# 13hdmi_lcd.net
KiCad netlist of a schematic drawn in Altium Designer
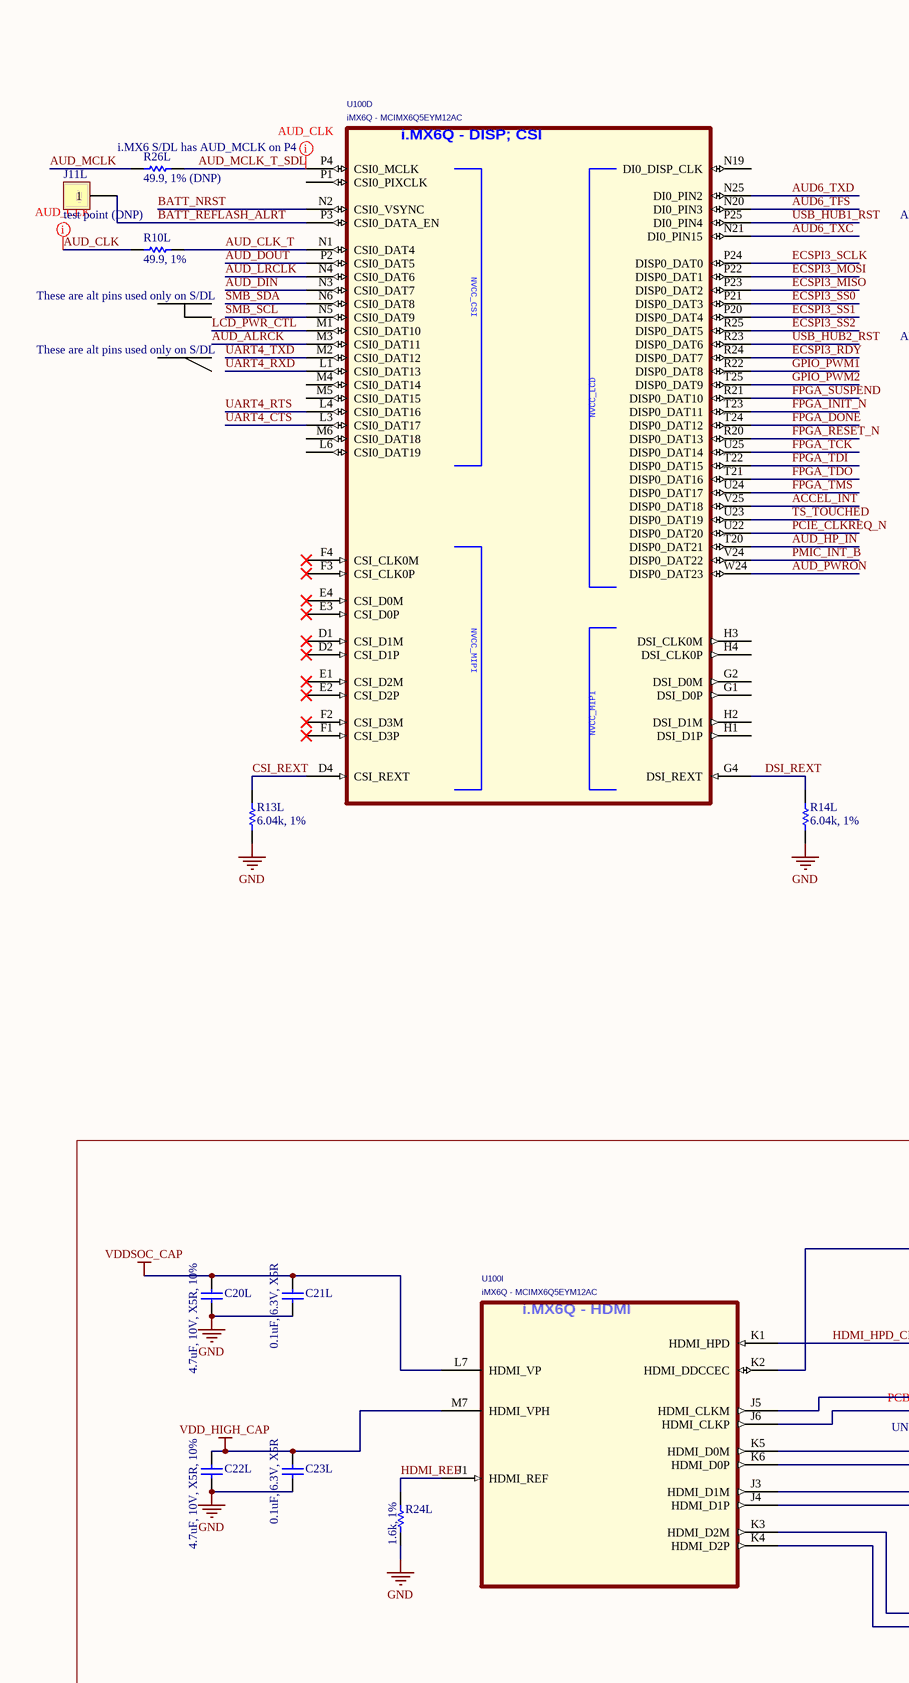
[diagram p0: 13hdmi_lcd.SchDoc, left]
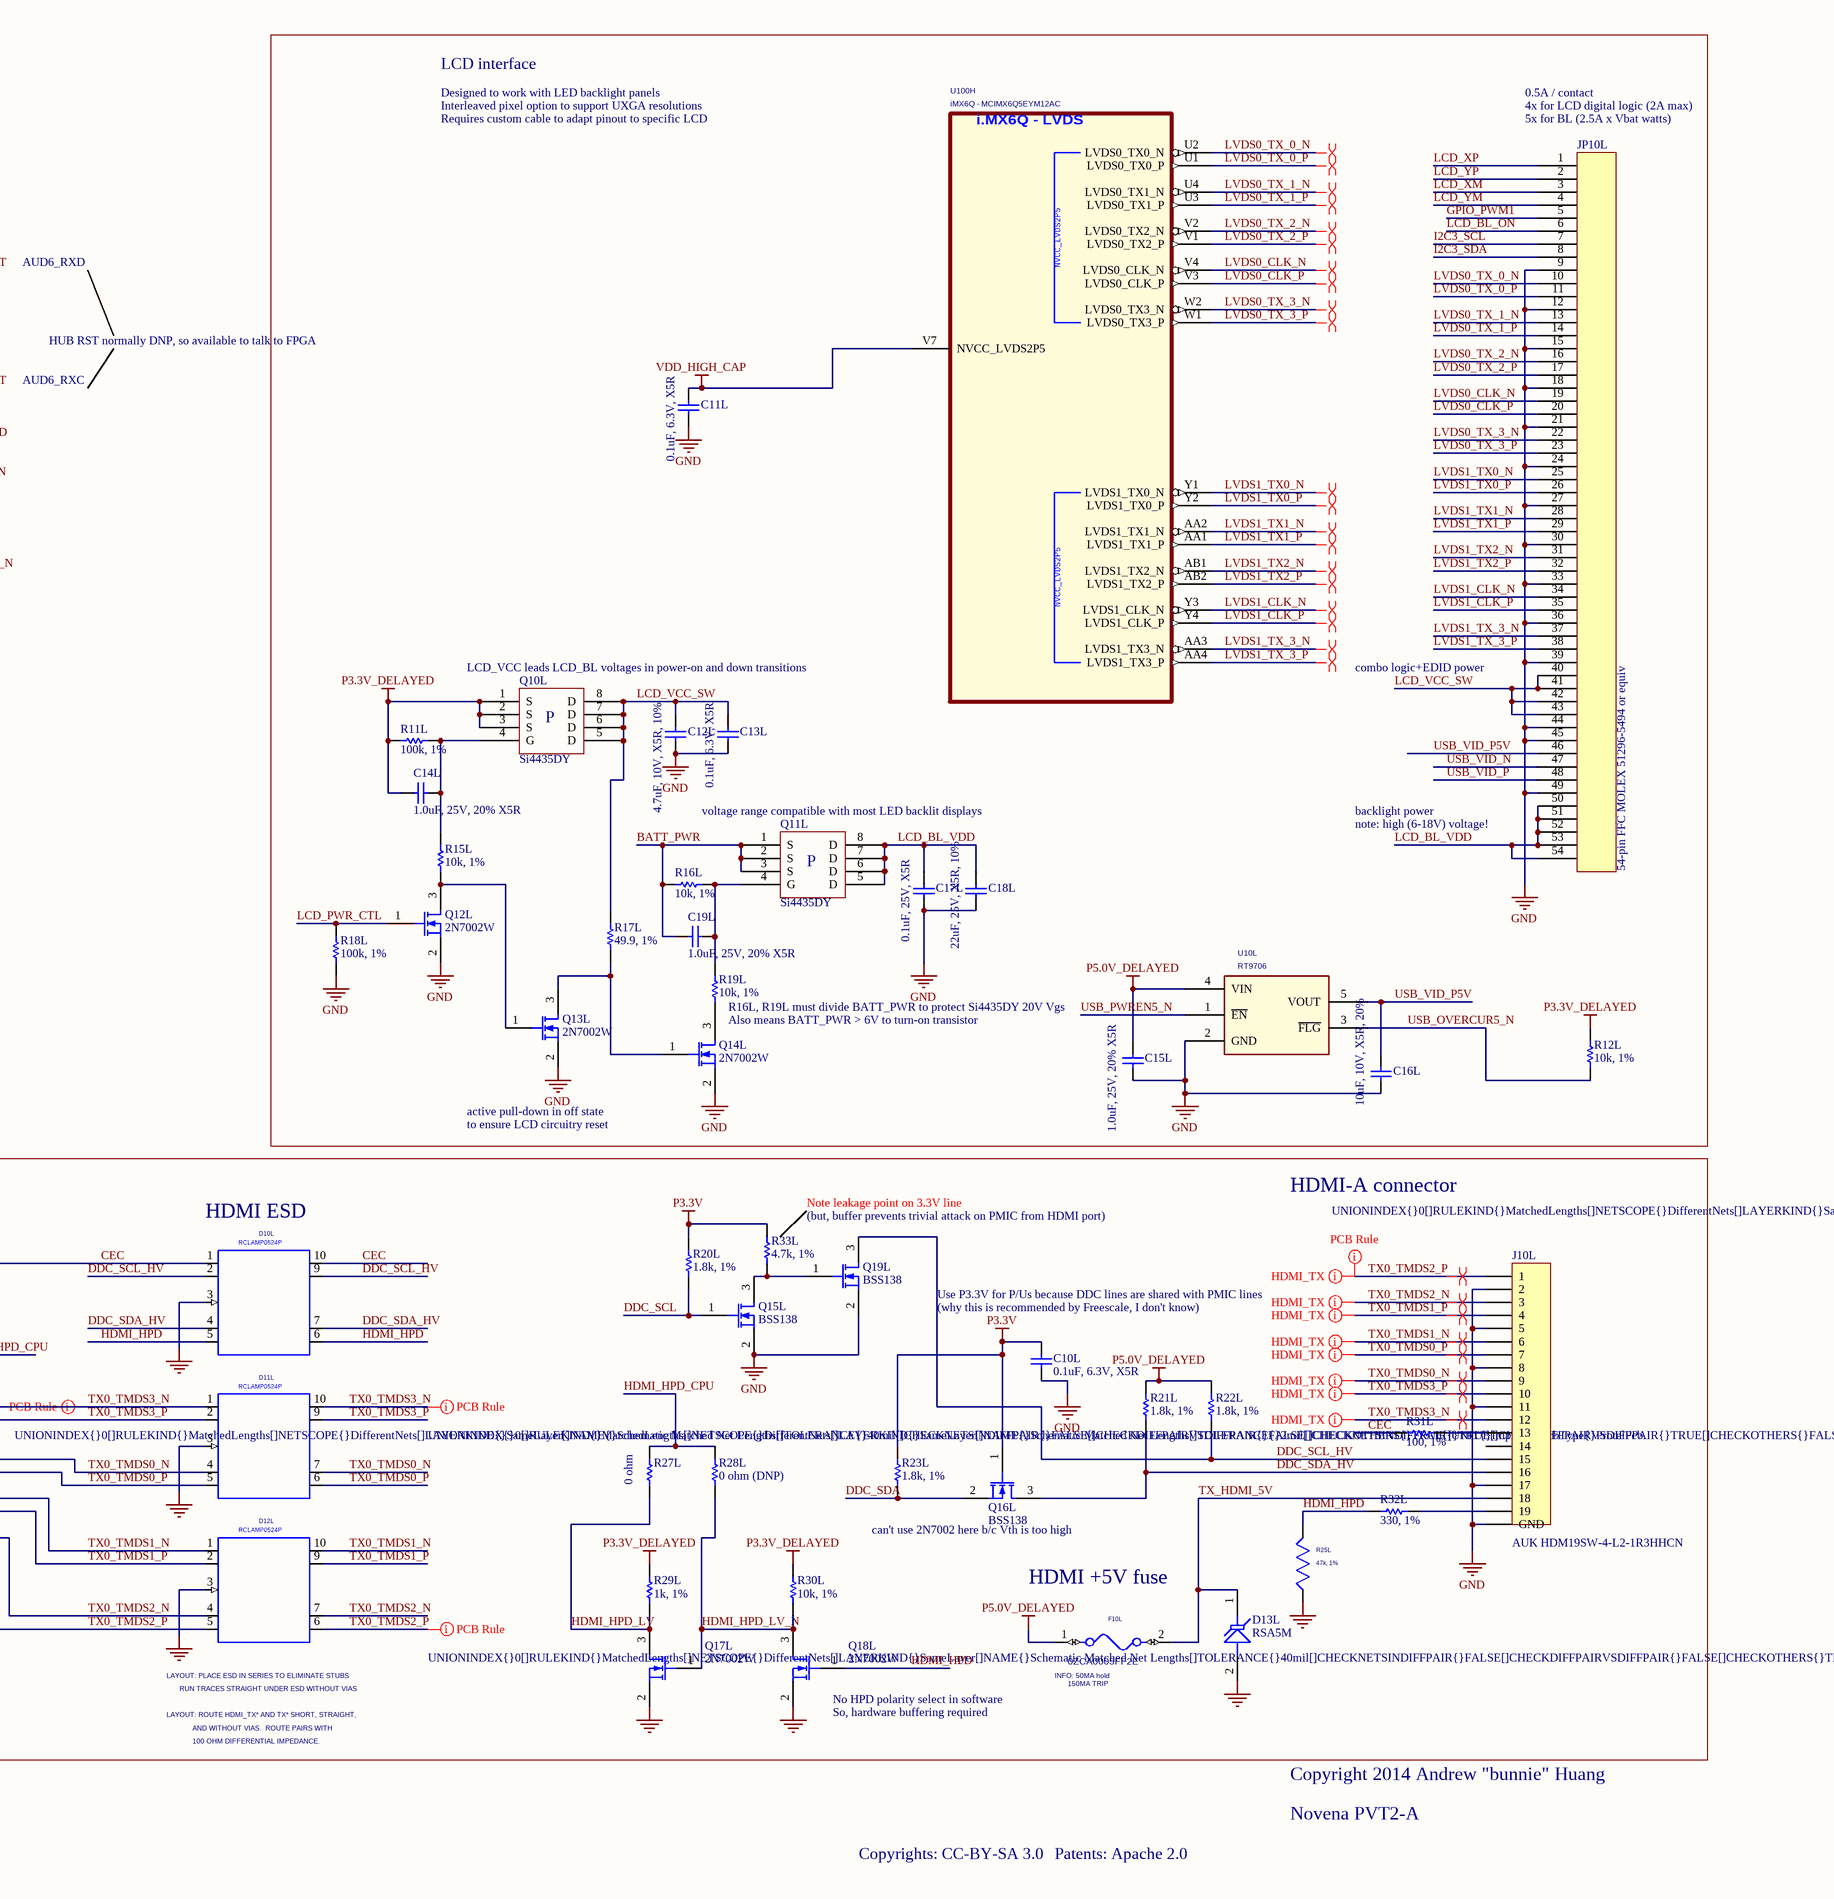
[diagram p1: 13hdmi_lcd.SchDoc, right]

(export (version "E")
  (design (tool "Eeschema 10.0.6"))
  (components
    (comp (ref "C10L")
      (value "0.1uF, 6.3V, X5R")
      (footprint "CAPC0603N_B")
      (description "Capacitor (Semiconductor SIM Model)")
      (fields (field (name "PUBLISHER") "Altium Limited"))
      (libsource (lib "Miscellaneous Devices") (part "Cap Semi"))
    )
    (comp (ref "C11L")
      (value "0.1uF, 6.3V, X5R")
      (footprint "CAPC0603N_B")
      (description "Capacitor (Semiconductor SIM Model)")
      (fields (field (name "PUBLISHER") "Altium Limited"))
      (libsource (lib "Miscellaneous Devices") (part "Cap Semi"))
    )
    (comp (ref "C12L")
      (value "4.7uF, 10V, X5R, 10%")
      (footprint "CAPC1608N")
      (description "Capacitor (Semiconductor SIM Model)")
      (fields (field (name "PUBLISHER") "Altium Limited"))
      (libsource (lib "Miscellaneous Devices") (part "Cap Semi"))
    )
    (comp (ref "C13L")
      (value "0.1uF, 6.3V, X5R")
      (footprint "CAPC0603N_B")
      (description "Capacitor (Semiconductor SIM Model)")
      (fields (field (name "PUBLISHER") "Altium Limited"))
      (libsource (lib "Miscellaneous Devices") (part "Cap Semi"))
    )
    (comp (ref "C14L")
      (value "1.0uF, 25V, 20% X5R")
      (footprint "CAPC1608N")
      (description "Capacitor (Semiconductor SIM Model)")
      (fields (field (name "PUBLISHER") "Altium Limited"))
      (libsource (lib "Miscellaneous Devices") (part "Cap Semi"))
    )
    (comp (ref "C15L")
      (value "1.0uF, 25V, 20% X5R")
      (footprint "CAPC1608N")
      (description "Capacitor (Semiconductor SIM Model)")
      (fields (field (name "PUBLISHER") "Altium Limited"))
      (libsource (lib "Miscellaneous Devices") (part "Cap Semi"))
    )
    (comp (ref "C16L")
      (value "10uF, 10V, X5R, 20%")
      (footprint "CAPC1608N")
      (description "Capacitor (Semiconductor SIM Model)")
      (fields (field (name "PUBLISHER") "Altium Limited"))
      (libsource (lib "Miscellaneous Devices") (part "Cap Semi"))
    )
    (comp (ref "C17L")
      (value "0.1uF, 25V, X5R")
      (footprint "CAPC1005N")
      (description "Capacitor (Semiconductor SIM Model)")
      (fields (field (name "PUBLISHER") "Altium Limited"))
      (libsource (lib "Miscellaneous Devices") (part "Cap Semi"))
    )
    (comp (ref "C18L")
      (value "22uF, 25V, X5R, 10%")
      (footprint "CAPC3225N")
      (description "Capacitor (Semiconductor SIM Model)")
      (fields (field (name "PUBLISHER") "Altium Limited"))
      (libsource (lib "Miscellaneous Devices") (part "Cap Semi"))
    )
    (comp (ref "C19L")
      (value "1.0uF, 25V, 20% X5R")
      (footprint "CAPC1608N")
      (description "Capacitor (Semiconductor SIM Model)")
      (fields (field (name "PUBLISHER") "Altium Limited"))
      (libsource (lib "Miscellaneous Devices") (part "Cap Semi"))
    )
    (comp (ref "C20L")
      (value "4.7uF, 10V, X5R, 10%")
      (footprint "CAPC1608N_HD")
      (description "Capacitor (Semiconductor SIM Model)")
      (fields (field (name "PUBLISHER") "Altium Limited"))
      (libsource (lib "Miscellaneous Devices") (part "Cap Semi"))
    )
    (comp (ref "C21L")
      (value "0.1uF, 6.3V, X5R")
      (footprint "CAPC0603N_B")
      (description "Capacitor (Semiconductor SIM Model)")
      (fields (field (name "PUBLISHER") "Altium Limited"))
      (libsource (lib "Miscellaneous Devices") (part "Cap Semi"))
    )
    (comp (ref "C22L")
      (value "4.7uF, 10V, X5R, 10%")
      (footprint "CAPC1608N_HD")
      (description "Capacitor (Semiconductor SIM Model)")
      (fields (field (name "PUBLISHER") "Altium Limited"))
      (libsource (lib "Miscellaneous Devices") (part "Cap Semi"))
    )
    (comp (ref "C23L")
      (value "0.1uF, 6.3V, X5R")
      (footprint "CAPC0603N_B")
      (description "Capacitor (Semiconductor SIM Model)")
      (fields (field (name "PUBLISHER") "Altium Limited"))
      (libsource (lib "Miscellaneous Devices") (part "Cap Semi"))
    )
    (comp (ref "D10L")
      (value "RCLAMP0524P")
      (fields (field (name "PART_NUMBER") "V00004-001"))
      (libsource (lib "*") (part "RCLAMP0524P"))
    )
    (comp (ref "D11L")
      (value "RCLAMP0524P")
      (fields (field (name "PART_NUMBER") "V00004-001"))
      (libsource (lib "*") (part "RCLAMP0524P"))
    )
    (comp (ref "D12L")
      (value "RCLAMP0524P")
      (fields (field (name "PART_NUMBER") "V00004-001"))
      (libsource (lib "*") (part "RCLAMP0524P"))
    )
    (comp (ref "D13L")
      (value "RSA5M")
      (footprint "SOD123/X.85")
      (description "Tranzorb")
      (fields (field (name "PUBLISHER") "Altium Limited"))
      (libsource (lib "Miscellaneous Devices") (part "Tranzorb"))
    )
    (comp (ref "F10L")
      (value "0ZCA0005FF2E")
      (description "BelFuse, 50mA hold, 150mA trip")
      (fields (field (name "PART_NUMBER") "M00014-001"))
      (libsource (lib "*") (part "FUSE0805"))
    )
    (comp (ref "J10L")
      (value "AUK HDM19SW-4-L2-1R3HHCN")
      (footprint "MOLEX_47151-0001")
      (description "Molex HDMI connector, Type A")
      (fields (field (name "PUBLISHER") "Altium Limited"))
      (libsource (lib "Miscellaneous Connectors") (part "Header 19"))
    )
    (comp (ref "J11L")
      (value "test point (DNP)")
      (footprint "TP_SMT_38mil")
      (description "Connector")
      (libsource (lib "*") (part "CON1"))
    )
    (comp (ref "JP10L")
      (value "54-pin FFC MOLEX 51296-5494 or equiv")
      (footprint "MOLEX_51296_5494")
      (description "Flat flex connector, 54 positions")
      (libsource (lib "commonsch") (part "HEADER_54"))
    )
    (comp (ref "Q10L")
      (value "Si4435DY")
      (footprint "SOIC127P600-8AN")
      (description "Singre P-channel FET, 8A, 30V")
      (libsource (lib "commonsch") (part "Si4435DY"))
    )
    (comp (ref "Q11L")
      (value "Si4435DY")
      (footprint "SOIC127P600-8AN")
      (description "Singre P-channel FET, 8A, 30V")
      (libsource (lib "commonsch") (part "Si4435DY"))
    )
    (comp (ref "Q12L")
      (value "2N7002W")
      (footprint "SOT323-3AN")
      (description "N-Channel MOSFET")
      (fields (field (name "PUBLISHER") "Altium Limited"))
      (libsource (lib "Miscellaneous Devices") (part "MOSFET-N"))
    )
    (comp (ref "Q13L")
      (value "2N7002W")
      (footprint "SOT323-3AN")
      (description "N-Channel MOSFET")
      (fields (field (name "PUBLISHER") "Altium Limited"))
      (libsource (lib "Miscellaneous Devices") (part "MOSFET-N"))
    )
    (comp (ref "Q14L")
      (value "2N7002W")
      (footprint "SOT323-3AN")
      (description "N-Channel MOSFET")
      (fields (field (name "PUBLISHER") "Altium Limited"))
      (libsource (lib "Miscellaneous Devices") (part "MOSFET-N"))
    )
    (comp (ref "Q15L")
      (value "BSS138")
      (footprint "SOT23-3N")
      (description "N-Channel MOSFET")
      (fields (field (name "PUBLISHER") "Altium Limited"))
      (libsource (lib "Miscellaneous Devices") (part "MOSFET-N"))
    )
    (comp (ref "Q16L")
      (value "BSS138")
      (footprint "SOT23-3N")
      (description "N-Channel MOSFET")
      (fields (field (name "PUBLISHER") "Altium Limited"))
      (libsource (lib "Miscellaneous Devices") (part "MOSFET-N"))
    )
    (comp (ref "Q17L")
      (value "2N7002W")
      (footprint "SOT323-3AN")
      (description "N-Channel MOSFET")
      (fields (field (name "PUBLISHER") "Altium Limited"))
      (libsource (lib "Miscellaneous Devices") (part "MOSFET-N"))
    )
    (comp (ref "Q18L")
      (value "2N7002W")
      (footprint "SOT323-3AN")
      (description "N-Channel MOSFET")
      (fields (field (name "PUBLISHER") "Altium Limited"))
      (libsource (lib "Miscellaneous Devices") (part "MOSFET-N"))
    )
    (comp (ref "Q19L")
      (value "BSS138")
      (footprint "SOT23-3N")
      (description "N-Channel MOSFET")
      (fields (field (name "PUBLISHER") "Altium Limited"))
      (libsource (lib "Miscellaneous Devices") (part "MOSFET-N"))
    )
    (comp (ref "R10L")
      (value "49.9, 1%")
      (footprint "RESC1005N")
      (description "Resistor")
      (fields (field (name "PUBLISHER") "Altium Limited"))
      (libsource (lib "Miscellaneous Devices") (part "Res1"))
    )
    (comp (ref "R11L")
      (value "100k, 1%")
      (footprint "RESC1005N")
      (description "Resistor")
      (fields (field (name "PUBLISHER") "Altium Limited"))
      (libsource (lib "Miscellaneous Devices") (part "Res1"))
    )
    (comp (ref "R12L")
      (value "10k, 1%")
      (footprint "RESC1005N")
      (description "Resistor")
      (fields (field (name "PUBLISHER") "Altium Limited"))
      (libsource (lib "Miscellaneous Devices") (part "Res1"))
    )
    (comp (ref "R13L")
      (value "6.04k, 1%")
      (footprint "RESC1005N")
      (description "Resistor")
      (fields (field (name "PUBLISHER") "Altium Limited"))
      (libsource (lib "Miscellaneous Devices") (part "Res1"))
    )
    (comp (ref "R14L")
      (value "6.04k, 1%")
      (footprint "RESC1005N")
      (description "Resistor")
      (fields (field (name "PUBLISHER") "Altium Limited"))
      (libsource (lib "Miscellaneous Devices") (part "Res1"))
    )
    (comp (ref "R15L")
      (value "10k, 1%")
      (footprint "RESC1005N")
      (description "Resistor")
      (fields (field (name "PUBLISHER") "Altium Limited"))
      (libsource (lib "Miscellaneous Devices") (part "Res1"))
    )
    (comp (ref "R16L")
      (value "10k, 1%")
      (footprint "RESC1005N")
      (description "Resistor")
      (fields (field (name "PUBLISHER") "Altium Limited"))
      (libsource (lib "Miscellaneous Devices") (part "Res1"))
    )
    (comp (ref "R17L")
      (value "49.9, 1%")
      (footprint "RESC1005N")
      (description "Resistor")
      (fields (field (name "PUBLISHER") "Altium Limited"))
      (libsource (lib "Miscellaneous Devices") (part "Res1"))
    )
    (comp (ref "R18L")
      (value "100k, 1%")
      (footprint "RESC1005N")
      (description "Resistor")
      (fields (field (name "PUBLISHER") "Altium Limited"))
      (libsource (lib "Miscellaneous Devices") (part "Res1"))
    )
    (comp (ref "R19L")
      (value "10k, 1%")
      (footprint "RESC1005N")
      (description "Resistor")
      (fields (field (name "PUBLISHER") "Altium Limited"))
      (libsource (lib "Miscellaneous Devices") (part "Res1"))
    )
    (comp (ref "R20L")
      (value "1.8k, 1%")
      (footprint "RESC1005N")
      (description "Resistor")
      (fields (field (name "PUBLISHER") "Altium Limited"))
      (libsource (lib "Miscellaneous Devices") (part "Res1"))
    )
    (comp (ref "R21L")
      (value "1.8k, 1%")
      (footprint "RESC1005N")
      (description "Resistor")
      (fields (field (name "PUBLISHER") "Altium Limited"))
      (libsource (lib "Miscellaneous Devices") (part "Res1"))
    )
    (comp (ref "R22L")
      (value "1.8k, 1%")
      (footprint "RESC1005N")
      (description "Resistor")
      (fields (field (name "PUBLISHER") "Altium Limited"))
      (libsource (lib "Miscellaneous Devices") (part "Res1"))
    )
    (comp (ref "R23L")
      (value "1.8k, 1%")
      (footprint "RESC1005N")
      (description "Resistor")
      (fields (field (name "PUBLISHER") "Altium Limited"))
      (libsource (lib "Miscellaneous Devices") (part "Res1"))
    )
    (comp (ref "R24L")
      (value "1.6k, 1%")
      (footprint "RESC1005N")
      (description "Resistor")
      (fields (field (name "PUBLISHER") "Altium Limited"))
      (libsource (lib "Miscellaneous Devices") (part "Res1"))
    )
    (comp (ref "R25L")
      (value "47k, 1%")
      (fields (field (name "PART_NUMBER") "D13015-001") (field (name "MFG") "PANASONIC"))
      (libsource (lib "*") (part "RES#1"))
    )
    (comp (ref "R26L")
      (value "49.9, 1% (DNP)")
      (footprint "RESC1005N")
      (description "Resistor")
      (fields (field (name "PUBLISHER") "Altium Limited"))
      (libsource (lib "Miscellaneous Devices") (part "Res1"))
    )
    (comp (ref "R27L")
      (value "0 ohm")
      (footprint "RESC1005N")
      (description "Resistor")
      (fields (field (name "PUBLISHER") "Altium Limited"))
      (libsource (lib "Miscellaneous Devices") (part "Res1"))
    )
    (comp (ref "R28L")
      (value "0 ohm (DNP)")
      (footprint "RESC1005N")
      (description "Resistor")
      (fields (field (name "PUBLISHER") "Altium Limited"))
      (libsource (lib "Miscellaneous Devices") (part "Res1"))
    )
    (comp (ref "R29L")
      (value "1k, 1%")
      (footprint "RESC1005N")
      (description "Resistor")
      (fields (field (name "PUBLISHER") "Altium Limited"))
      (libsource (lib "Miscellaneous Devices") (part "Res1"))
    )
    (comp (ref "R30L")
      (value "10k, 1%")
      (footprint "RESC1005N")
      (description "Resistor")
      (fields (field (name "PUBLISHER") "Altium Limited"))
      (libsource (lib "Miscellaneous Devices") (part "Res1"))
    )
    (comp (ref "R31L")
      (value "100, 1%")
      (footprint "RESC1005N")
      (description "Resistor")
      (fields (field (name "PUBLISHER") "Altium Limited"))
      (libsource (lib "Miscellaneous Devices") (part "Res1"))
    )
    (comp (ref "R32L")
      (value "330, 1%")
      (footprint "RESC1005N")
      (description "Resistor")
      (fields (field (name "PUBLISHER") "Altium Limited"))
      (libsource (lib "Miscellaneous Devices") (part "Res1"))
    )
    (comp (ref "R33L")
      (value "4.7k, 1%")
      (footprint "RESC1005N")
      (description "Resistor")
      (fields (field (name "PUBLISHER") "Altium Limited"))
      (libsource (lib "Miscellaneous Devices") (part "Res1"))
    )
    (comp (ref "U10L")
      (value "RT9706")
      (description "IC LIN SW W/FLAG 500MA 2.0-5.5V SOT23-5")
      (libsource (lib "*") (part "RT9706"))
    )
    (comp (ref "U100")
      (value "iMX6Q - MCIMX6Q5EYM12AC")
      (description "PCIMX6Q5EVT10AC")
      (libsource (lib "*") (part "PCIMX6Q6VV1A"))
    )
  )
  (nets
    (net (code "1") (name "/ACCEL_INT") (class "Default")
      (node (ref "U100") (pin "V25") (pinfunction "DISP0_DAT18_V25") (pintype "bidirectional"))
    )
    (net (code "2") (name "/AUD6_TFS") (class "Default")
      (node (ref "U100") (pin "N20") (pinfunction "DI0_PIN3_N20") (pintype "bidirectional"))
    )
    (net (code "3") (name "/AUD6_TXC") (class "Default")
      (node (ref "U100") (pin "N21") (pinfunction "DI0_PIN15_N21") (pintype "bidirectional"))
    )
    (net (code "4") (name "/AUD6_TXD") (class "Default")
      (node (ref "U100") (pin "N25") (pinfunction "DI0_PIN2_N25") (pintype "bidirectional"))
    )
    (net (code "5") (name "/AUD_ALRCK") (class "Default")
      (node (ref "U100") (pin "M3") (pinfunction "CSI0_DAT11_M3") (pintype "bidirectional"))
    )
    (net (code "6") (name "/AUD_CLK") (class "Default")
      (node (ref "R10L") (pin "2") (pinfunction "2_2") (pintype "passive"))
    )
    (net (code "7") (name "/AUD_CLK_T") (class "Default")
      (node (ref "R10L") (pin "1") (pinfunction "1_1") (pintype "passive"))
      (node (ref "U100") (pin "N1") (pinfunction "CSI0_DAT4_N1") (pintype "bidirectional"))
    )
    (net (code "8") (name "/AUD_DIN") (class "Default")
      (node (ref "U100") (pin "N3") (pinfunction "CSI0_DAT7_N3") (pintype "bidirectional"))
    )
    (net (code "9") (name "/AUD_DOUT") (class "Default")
      (node (ref "U100") (pin "P2") (pinfunction "CSI0_DAT5_P2") (pintype "bidirectional"))
    )
    (net (code "10") (name "/AUD_HP_IN") (class "Default")
      (node (ref "U100") (pin "T20") (pinfunction "DISP0_DAT21_T20") (pintype "bidirectional"))
    )
    (net (code "11") (name "/AUD_LRCLK") (class "Default")
      (node (ref "U100") (pin "N4") (pinfunction "CSI0_DAT6_N4") (pintype "bidirectional"))
    )
    (net (code "12") (name "/AUD_MCLK") (class "Default")
      (node (ref "R26L") (pin "2") (pinfunction "2_2") (pintype "passive"))
    )
    (net (code "13") (name "/AUD_MCLK_T_SDL") (class "Default")
      (node (ref "R26L") (pin "1") (pinfunction "1_1") (pintype "passive"))
      (node (ref "U100") (pin "P4") (pinfunction "CSI0_MCLK_P4") (pintype "bidirectional"))
    )
    (net (code "14") (name "/AUD_PWRON") (class "Default")
      (node (ref "U100") (pin "W24") (pinfunction "DISP0_DAT23_W24") (pintype "bidirectional"))
    )
    (net (code "15") (name "/BATT_NRST") (class "Default")
      (node (ref "U100") (pin "N2") (pinfunction "CSI0_VSYNC_N2") (pintype "bidirectional"))
    )
    (net (code "16") (name "/BATT_PWR") (class "Default")
      (node (ref "C19L") (pin "1") (pinfunction "1_1") (pintype "passive"))
      (node (ref "Q11L") (pin "1") (pinfunction "S_1") (pintype "passive"))
      (node (ref "Q11L") (pin "2") (pinfunction "S_2") (pintype "passive"))
      (node (ref "Q11L") (pin "3") (pinfunction "S_3") (pintype "passive"))
      (node (ref "R16L") (pin "2") (pinfunction "2_2") (pintype "passive"))
    )
    (net (code "17") (name "/BATT_REFLASH_ALRT") (class "Default")
      (node (ref "J11L") (pin "1") (pinfunction "1_1") (pintype "passive"))
      (node (ref "U100") (pin "P3") (pinfunction "CSI0_DATA_EN_P3") (pintype "bidirectional"))
    )
    (net (code "18") (name "/CEC") (class "Default")
      (node (ref "D10L") (pin "1") (pinfunction "IO1A_1") (pintype "bidirectional"))
      (node (ref "D10L") (pin "10") (pinfunction "IO1B_10") (pintype "bidirectional"))
      (node (ref "R31L") (pin "2") (pinfunction "2_2") (pintype "passive"))
      (node (ref "U100") (pin "K2") (pinfunction "HDMI_DDCCEC_K2") (pintype "bidirectional"))
    )
    (net (code "19") (name "/CSI_REXT") (class "Default")
      (node (ref "R13L") (pin "1") (pinfunction "1_1") (pintype "passive"))
      (node (ref "U100") (pin "D4") (pinfunction "CSI_REXT_D4") (pintype "input"))
    )
    (net (code "20") (name "/DDC_SCL") (class "Default")
      (node (ref "Q15L") (pin "1") (pinfunction "G_1") (pintype "passive"))
      (node (ref "R20L") (pin "2") (pinfunction "2_2") (pintype "passive"))
    )
    (net (code "21") (name "/DDC_SCL_HV") (class "Default")
      (node (ref "D10L") (pin "2") (pinfunction "IO2A_2") (pintype "bidirectional"))
      (node (ref "D10L") (pin "9") (pinfunction "IO2B_9") (pintype "bidirectional"))
      (node (ref "J10L") (pin "15") (pinfunction "15_15") (pintype "passive"))
      (node (ref "Q19L") (pin "3") (pinfunction "D_3") (pintype "passive"))
      (node (ref "R22L") (pin "2") (pinfunction "2_2") (pintype "passive"))
    )
    (net (code "22") (name "/DDC_SDA") (class "Default")
      (node (ref "Q16L") (pin "2") (pinfunction "S_2") (pintype "passive"))
      (node (ref "R23L") (pin "2") (pinfunction "2_2") (pintype "passive"))
    )
    (net (code "23") (name "/DDC_SDA_HV") (class "Default")
      (node (ref "D10L") (pin "4") (pinfunction "IO3A_4") (pintype "bidirectional"))
      (node (ref "D10L") (pin "7") (pinfunction "IO3B_7") (pintype "bidirectional"))
      (node (ref "J10L") (pin "16") (pinfunction "16_16") (pintype "passive"))
      (node (ref "Q16L") (pin "3") (pinfunction "D_3") (pintype "passive"))
      (node (ref "R21L") (pin "2") (pinfunction "2_2") (pintype "passive"))
    )
    (net (code "24") (name "/DSI_REXT") (class "Default")
      (node (ref "R14L") (pin "1") (pinfunction "1_1") (pintype "passive"))
      (node (ref "U100") (pin "G4") (pinfunction "DSI_REXT_G4") (pintype "input"))
    )
    (net (code "25") (name "/ECSPI3_MISO") (class "Default")
      (node (ref "U100") (pin "P23") (pinfunction "DISP0_DAT2_P23") (pintype "bidirectional"))
    )
    (net (code "26") (name "/ECSPI3_MOSI") (class "Default")
      (node (ref "U100") (pin "P22") (pinfunction "DISP0_DAT1_P22") (pintype "bidirectional"))
    )
    (net (code "27") (name "/ECSPI3_RDY") (class "Default")
      (node (ref "U100") (pin "R24") (pinfunction "DISP0_DAT7_R24") (pintype "bidirectional"))
    )
    (net (code "28") (name "/ECSPI3_SCLK") (class "Default")
      (node (ref "U100") (pin "P24") (pinfunction "DISP0_DAT0_P24") (pintype "bidirectional"))
    )
    (net (code "29") (name "/ECSPI3_SS0") (class "Default")
      (node (ref "U100") (pin "P21") (pinfunction "DISP0_DAT3_P21") (pintype "bidirectional"))
    )
    (net (code "30") (name "/ECSPI3_SS1") (class "Default")
      (node (ref "U100") (pin "P20") (pinfunction "DISP0_DAT4_P20") (pintype "bidirectional"))
    )
    (net (code "31") (name "/ECSPI3_SS2") (class "Default")
      (node (ref "U100") (pin "R25") (pinfunction "DISP0_DAT5_R25") (pintype "bidirectional"))
    )
    (net (code "32") (name "/FPGA_DONE") (class "Default")
      (node (ref "U100") (pin "T24") (pinfunction "DISP0_DAT12_T24") (pintype "bidirectional"))
    )
    (net (code "33") (name "/FPGA_INIT_N") (class "Default")
      (node (ref "U100") (pin "T23") (pinfunction "DISP0_DAT11_T23") (pintype "bidirectional"))
    )
    (net (code "34") (name "/FPGA_RESET_N") (class "Default")
      (node (ref "U100") (pin "R20") (pinfunction "DISP0_DAT13_R20") (pintype "bidirectional"))
    )
    (net (code "35") (name "/FPGA_SUSPEND") (class "Default")
      (node (ref "U100") (pin "R21") (pinfunction "DISP0_DAT10_R21") (pintype "bidirectional"))
    )
    (net (code "36") (name "/FPGA_TCK") (class "Default")
      (node (ref "U100") (pin "U25") (pinfunction "DISP0_DAT14_U25") (pintype "bidirectional"))
    )
    (net (code "37") (name "/FPGA_TDI") (class "Default")
      (node (ref "U100") (pin "T22") (pinfunction "DISP0_DAT15_T22") (pintype "bidirectional"))
    )
    (net (code "38") (name "/FPGA_TDO") (class "Default")
      (node (ref "U100") (pin "T21") (pinfunction "DISP0_DAT16_T21") (pintype "bidirectional"))
    )
    (net (code "39") (name "/FPGA_TMS") (class "Default")
      (node (ref "U100") (pin "U24") (pinfunction "DISP0_DAT17_U24") (pintype "bidirectional"))
    )
    (net (code "40") (name "/GPIO_PWM1") (class "Default")
      (node (ref "JP10L") (pin "5") (pintype "passive"))
      (node (ref "U100") (pin "R22") (pinfunction "DISP0_DAT8_R22") (pintype "bidirectional"))
    )
    (net (code "41") (name "/GPIO_PWM2") (class "Default")
      (node (ref "U100") (pin "T25") (pinfunction "DISP0_DAT9_T25") (pintype "bidirectional"))
    )
    (net (code "42") (name "/HDMI_HPD") (class "Default")
      (node (ref "D10L") (pin "5") (pinfunction "IO4A_5") (pintype "bidirectional"))
      (node (ref "D10L") (pin "6") (pinfunction "IO4B_6") (pintype "bidirectional"))
      (node (ref "Q18L") (pin "1") (pinfunction "G_1") (pintype "passive"))
      (node (ref "R25L") (pin "1") (pinfunction "A_1") (pintype "bidirectional"))
      (node (ref "R32L") (pin "2") (pinfunction "2_2") (pintype "passive"))
    )
    (net (code "43") (name "/HDMI_HPD_CPU") (class "Default")
      (node (ref "R27L") (pin "1") (pinfunction "1_1") (pintype "passive"))
      (node (ref "R28L") (pin "1") (pinfunction "1_1") (pintype "passive"))
      (node (ref "U100") (pin "K1") (pinfunction "HDMI_HPD_K1") (pintype "input"))
    )
    (net (code "44") (name "/HDMI_HPD_LV") (class "Default")
      (node (ref "Q17L") (pin "3") (pinfunction "D_3") (pintype "passive"))
      (node (ref "R27L") (pin "2") (pinfunction "2_2") (pintype "passive"))
      (node (ref "R29L") (pin "2") (pinfunction "2_2") (pintype "passive"))
    )
    (net (code "45") (name "/HDMI_HPD_LV_N") (class "Default")
      (node (ref "Q17L") (pin "1") (pinfunction "G_1") (pintype "passive"))
      (node (ref "Q18L") (pin "3") (pinfunction "D_3") (pintype "passive"))
      (node (ref "R28L") (pin "2") (pinfunction "2_2") (pintype "passive"))
      (node (ref "R30L") (pin "2") (pinfunction "2_2") (pintype "passive"))
    )
    (net (code "46") (name "/HDMI_REF") (class "Default")
      (node (ref "R24L") (pin "2") (pinfunction "2_2") (pintype "passive"))
      (node (ref "U100") (pin "J1") (pinfunction "HDMI_REF_J1") (pintype "input"))
    )
    (net (code "47") (name "/I2C3_SCL") (class "Default") (node (ref "JP10L") (pin "7") (pintype "passive")))
    (net (code "48") (name "/I2C3_SDA") (class "Default") (node (ref "JP10L") (pin "8") (pintype "passive")))
    (net (code "49") (name "/LCD_BL_ON") (class "Default") (node (ref "JP10L") (pin "6") (pintype "passive")))
    (net (code "50") (name "/LCD_BL_VDD") (class "Default")
      (node (ref "C17L") (pin "1") (pinfunction "1_1") (pintype "passive"))
      (node (ref "C18L") (pin "1") (pinfunction "1_1") (pintype "passive"))
      (node (ref "JP10L") (pin "50") (pintype "passive"))
      (node (ref "JP10L") (pin "51") (pintype "passive"))
      (node (ref "JP10L") (pin "52") (pintype "passive"))
      (node (ref "JP10L") (pin "53") (pintype "passive"))
      (node (ref "JP10L") (pin "54") (pintype "passive"))
      (node (ref "Q11L") (pin "5") (pinfunction "D_5") (pintype "passive"))
      (node (ref "Q11L") (pin "6") (pinfunction "D_6") (pintype "passive"))
      (node (ref "Q11L") (pin "7") (pinfunction "D_7") (pintype "passive"))
      (node (ref "Q11L") (pin "8") (pinfunction "D_8") (pintype "passive"))
    )
    (net (code "51") (name "/LCD_PWR_CTL") (class "Default")
      (node (ref "Q12L") (pin "1") (pinfunction "G_1") (pintype "passive"))
      (node (ref "R18L") (pin "2") (pinfunction "2_2") (pintype "passive"))
      (node (ref "U100") (pin "M1") (pinfunction "CSI0_DAT10_M1") (pintype "bidirectional"))
    )
    (net (code "52") (name "/LCD_VCC_SW") (class "Default")
      (node (ref "C12L") (pin "1") (pinfunction "1_1") (pintype "passive"))
      (node (ref "C13L") (pin "1") (pinfunction "1_1") (pintype "passive"))
      (node (ref "JP10L") (pin "40") (pintype "passive"))
      (node (ref "JP10L") (pin "41") (pintype "passive"))
      (node (ref "JP10L") (pin "42") (pintype "passive"))
      (node (ref "JP10L") (pin "43") (pintype "passive"))
      (node (ref "Q10L") (pin "5") (pinfunction "D_5") (pintype "passive"))
      (node (ref "Q10L") (pin "6") (pinfunction "D_6") (pintype "passive"))
      (node (ref "Q10L") (pin "7") (pinfunction "D_7") (pintype "passive"))
      (node (ref "Q10L") (pin "8") (pinfunction "D_8") (pintype "passive"))
      (node (ref "R17L") (pin "2") (pinfunction "2_2") (pintype "passive"))
    )
    (net (code "53") (name "/LCD_XM") (class "Default") (node (ref "JP10L") (pin "3") (pintype "passive")))
    (net (code "54") (name "/LCD_XP") (class "Default") (node (ref "JP10L") (pin "1") (pintype "passive")))
    (net (code "55") (name "/LCD_YM") (class "Default") (node (ref "JP10L") (pin "4") (pintype "passive")))
    (net (code "56") (name "/LCD_YP") (class "Default") (node (ref "JP10L") (pin "2") (pintype "passive")))
    (net (code "57") (name "/LVDS0_CLK_N") (class "Default")
      (node (ref "JP10L") (pin "19") (pintype "passive"))
      (node (ref "U100") (pin "V4") (pinfunction "LVDS0_CLK_N_V4") (pintype "output"))
    )
    (net (code "58") (name "/LVDS0_CLK_P") (class "Default")
      (node (ref "JP10L") (pin "20") (pintype "passive"))
      (node (ref "U100") (pin "V3") (pinfunction "LVDS0_CLK_P_V3") (pintype "output"))
    )
    (net (code "59") (name "/LVDS0_TX_0_N") (class "Default")
      (node (ref "JP10L") (pin "10") (pintype "passive"))
      (node (ref "U100") (pin "U2") (pinfunction "LVDS0_TX0_N_U2") (pintype "output"))
    )
    (net (code "60") (name "/LVDS0_TX_0_P") (class "Default")
      (node (ref "JP10L") (pin "11") (pintype "passive"))
      (node (ref "U100") (pin "U1") (pinfunction "LVDS0_TX0_P_U1") (pintype "output"))
    )
    (net (code "61") (name "/LVDS0_TX_1_N") (class "Default")
      (node (ref "JP10L") (pin "13") (pintype "passive"))
      (node (ref "U100") (pin "U4") (pinfunction "LVDS0_TX1_N_U4") (pintype "output"))
    )
    (net (code "62") (name "/LVDS0_TX_1_P") (class "Default")
      (node (ref "JP10L") (pin "14") (pintype "passive"))
      (node (ref "U100") (pin "U3") (pinfunction "LVDS0_TX1_P_U3") (pintype "output"))
    )
    (net (code "63") (name "/LVDS0_TX_2_N") (class "Default")
      (node (ref "JP10L") (pin "16") (pintype "passive"))
      (node (ref "U100") (pin "V2") (pinfunction "LVDS0_TX2_N_V2") (pintype "output"))
    )
    (net (code "64") (name "/LVDS0_TX_2_P") (class "Default")
      (node (ref "JP10L") (pin "17") (pintype "passive"))
      (node (ref "U100") (pin "V1") (pinfunction "LVDS0_TX2_P_V1") (pintype "output"))
    )
    (net (code "65") (name "/LVDS0_TX_3_N") (class "Default")
      (node (ref "JP10L") (pin "22") (pintype "passive"))
      (node (ref "U100") (pin "W2") (pinfunction "LVDS0_TX3_N_W2") (pintype "output"))
    )
    (net (code "66") (name "/LVDS0_TX_3_P") (class "Default")
      (node (ref "JP10L") (pin "23") (pintype "passive"))
      (node (ref "U100") (pin "W1") (pinfunction "LVDS0_TX3_P_W1") (pintype "output"))
    )
    (net (code "67") (name "/LVDS1_CLK_N") (class "Default")
      (node (ref "JP10L") (pin "34") (pintype "passive"))
      (node (ref "U100") (pin "Y3") (pinfunction "LVDS1_CLK_N_Y3") (pintype "output"))
    )
    (net (code "68") (name "/LVDS1_CLK_P") (class "Default")
      (node (ref "JP10L") (pin "35") (pintype "passive"))
      (node (ref "U100") (pin "Y4") (pinfunction "LVDS1_CLK_P_Y4") (pintype "output"))
    )
    (net (code "69") (name "/LVDS1_TX0_N") (class "Default")
      (node (ref "JP10L") (pin "25") (pintype "passive"))
      (node (ref "U100") (pin "Y1") (pinfunction "LVDS1_TX0_N_Y1") (pintype "output"))
    )
    (net (code "70") (name "/LVDS1_TX0_P") (class "Default")
      (node (ref "JP10L") (pin "26") (pintype "passive"))
      (node (ref "U100") (pin "Y2") (pinfunction "LVDS1_TX0_P_Y2") (pintype "output"))
    )
    (net (code "71") (name "/LVDS1_TX1_N") (class "Default")
      (node (ref "JP10L") (pin "28") (pintype "passive"))
      (node (ref "U100") (pin "AA2") (pinfunction "LVDS1_TX1_N_AA2") (pintype "output"))
    )
    (net (code "72") (name "/LVDS1_TX1_P") (class "Default")
      (node (ref "JP10L") (pin "29") (pintype "passive"))
      (node (ref "U100") (pin "AA1") (pinfunction "LVDS1_TX1_P_AA1") (pintype "output"))
    )
    (net (code "73") (name "/LVDS1_TX2_N") (class "Default")
      (node (ref "JP10L") (pin "31") (pintype "passive"))
      (node (ref "U100") (pin "AB1") (pinfunction "LVDS1_TX2_N_AB1") (pintype "output"))
    )
    (net (code "74") (name "/LVDS1_TX2_P") (class "Default")
      (node (ref "JP10L") (pin "32") (pintype "passive"))
      (node (ref "U100") (pin "AB2") (pinfunction "LVDS1_TX2_P_AB2") (pintype "output"))
    )
    (net (code "75") (name "/LVDS1_TX_3_N") (class "Default")
      (node (ref "JP10L") (pin "37") (pintype "passive"))
      (node (ref "U100") (pin "AA3") (pinfunction "LVDS1_TX3_N_AA3") (pintype "output"))
    )
    (net (code "76") (name "/LVDS1_TX_3_P") (class "Default")
      (node (ref "JP10L") (pin "38") (pintype "passive"))
      (node (ref "U100") (pin "AA4") (pinfunction "LVDS1_TX3_P_AA4") (pintype "output"))
    )
    (net (code "77") (name "/PCIE_CLKREQ_N") (class "Default")
      (node (ref "U100") (pin "U22") (pinfunction "DISP0_DAT20_U22") (pintype "bidirectional"))
    )
    (net (code "78") (name "/PMIC_INT_B") (class "Default")
      (node (ref "U100") (pin "V24") (pinfunction "DISP0_DAT22_V24") (pintype "bidirectional"))
    )
    (net (code "79") (name "/SMB_SCL") (class "Default")
      (node (ref "U100") (pin "N5") (pinfunction "CSI0_DAT9_N5") (pintype "bidirectional"))
    )
    (net (code "80") (name "/SMB_SDA") (class "Default")
      (node (ref "U100") (pin "N6") (pinfunction "CSI0_DAT8_N6") (pintype "bidirectional"))
    )
    (net (code "81") (name "/TS_TOUCHED") (class "Default")
      (node (ref "U100") (pin "U23") (pinfunction "DISP0_DAT19_U23") (pintype "bidirectional"))
    )
    (net (code "82") (name "/TX0_TMDS0_N") (class "Default")
      (node (ref "D11L") (pin "4") (pinfunction "IO3A_4") (pintype "bidirectional"))
      (node (ref "D11L") (pin "7") (pinfunction "IO3B_7") (pintype "bidirectional"))
      (node (ref "J10L") (pin "9") (pinfunction "9_9") (pintype "passive"))
      (node (ref "U100") (pin "K5") (pinfunction "HDMI_D0M_K5") (pintype "output"))
    )
    (net (code "83") (name "/TX0_TMDS0_P") (class "Default")
      (node (ref "D11L") (pin "5") (pinfunction "IO4A_5") (pintype "bidirectional"))
      (node (ref "D11L") (pin "6") (pinfunction "IO4B_6") (pintype "bidirectional"))
      (node (ref "J10L") (pin "7") (pinfunction "7_7") (pintype "passive"))
      (node (ref "U100") (pin "K6") (pinfunction "HDMI_D0P_K6") (pintype "output"))
    )
    (net (code "84") (name "/TX0_TMDS1_N") (class "Default")
      (node (ref "D12L") (pin "1") (pinfunction "IO1A_1") (pintype "bidirectional"))
      (node (ref "D12L") (pin "10") (pinfunction "IO1B_10") (pintype "bidirectional"))
      (node (ref "J10L") (pin "6") (pinfunction "6_6") (pintype "passive"))
      (node (ref "U100") (pin "J3") (pinfunction "HDMI_D1M_J3") (pintype "output"))
    )
    (net (code "85") (name "/TX0_TMDS1_P") (class "Default")
      (node (ref "D12L") (pin "2") (pinfunction "IO2A_2") (pintype "bidirectional"))
      (node (ref "D12L") (pin "9") (pinfunction "IO2B_9") (pintype "bidirectional"))
      (node (ref "J10L") (pin "4") (pinfunction "4_4") (pintype "passive"))
      (node (ref "U100") (pin "J4") (pinfunction "HDMI_D1P_J4") (pintype "output"))
    )
    (net (code "86") (name "/TX0_TMDS2_N") (class "Default")
      (node (ref "D12L") (pin "4") (pinfunction "IO3A_4") (pintype "bidirectional"))
      (node (ref "D12L") (pin "7") (pinfunction "IO3B_7") (pintype "bidirectional"))
      (node (ref "J10L") (pin "3") (pinfunction "3_3") (pintype "passive"))
      (node (ref "U100") (pin "K3") (pinfunction "HDMI_D2M_K3") (pintype "output"))
    )
    (net (code "87") (name "/TX0_TMDS2_P") (class "Default")
      (node (ref "D12L") (pin "5") (pinfunction "IO4A_5") (pintype "bidirectional"))
      (node (ref "D12L") (pin "6") (pinfunction "IO4B_6") (pintype "bidirectional"))
      (node (ref "J10L") (pin "1") (pinfunction "1_1") (pintype "passive"))
      (node (ref "U100") (pin "K4") (pinfunction "HDMI_D2P_K4") (pintype "output"))
    )
    (net (code "88") (name "/TX0_TMDS3_N") (class "Default")
      (node (ref "D11L") (pin "1") (pinfunction "IO1A_1") (pintype "bidirectional"))
      (node (ref "D11L") (pin "10") (pinfunction "IO1B_10") (pintype "bidirectional"))
      (node (ref "J10L") (pin "12") (pinfunction "12_12") (pintype "passive"))
      (node (ref "U100") (pin "J5") (pinfunction "HDMI_CLKM_J5") (pintype "output"))
    )
    (net (code "89") (name "/TX0_TMDS3_P") (class "Default")
      (node (ref "D11L") (pin "2") (pinfunction "IO2A_2") (pintype "bidirectional"))
      (node (ref "D11L") (pin "9") (pinfunction "IO2B_9") (pintype "bidirectional"))
      (node (ref "J10L") (pin "10") (pinfunction "10_10") (pintype "passive"))
      (node (ref "U100") (pin "J6") (pinfunction "HDMI_CLKP_J6") (pintype "output"))
    )
    (net (code "90") (name "/TX_HDMI_5V") (class "Default")
      (node (ref "D13L") (pin "1") (pinfunction "K_1") (pintype "passive"))
      (node (ref "F10L") (pin "2") (pinfunction "2_2") (pintype "bidirectional"))
      (node (ref "J10L") (pin "18") (pinfunction "18_18") (pintype "passive"))
    )
    (net (code "91") (name "/UART4_CTS") (class "Default")
      (node (ref "U100") (pin "L3") (pinfunction "CSI0_DAT17_L3") (pintype "bidirectional"))
    )
    (net (code "92") (name "/UART4_RTS") (class "Default")
      (node (ref "U100") (pin "L4") (pinfunction "CSI0_DAT16_L4") (pintype "bidirectional"))
    )
    (net (code "93") (name "/UART4_RXD") (class "Default")
      (node (ref "U100") (pin "L1") (pinfunction "CSI0_DAT13_L1") (pintype "bidirectional"))
    )
    (net (code "94") (name "/UART4_TXD") (class "Default")
      (node (ref "U100") (pin "M2") (pinfunction "CSI0_DAT12_M2") (pintype "bidirectional"))
    )
    (net (code "95") (name "/USB_HUB1_RST") (class "Default")
      (node (ref "U100") (pin "P25") (pinfunction "DI0_PIN4_P25") (pintype "bidirectional"))
    )
    (net (code "96") (name "/USB_HUB2_RST") (class "Default")
      (node (ref "U100") (pin "R23") (pinfunction "DISP0_DAT6_R23") (pintype "bidirectional"))
    )
    (net (code "97") (name "/USB_OVERCUR5_N") (class "Default")
      (node (ref "R12L") (pin "1") (pinfunction "1_1") (pintype "passive"))
      (node (ref "U10L") (pin "3") (pinfunction "~{FLG}_3") (pintype "passive"))
    )
    (net (code "98") (name "/USB_PWREN5_N") (class "Default")
      (node (ref "U10L") (pin "1") (pinfunction "~{EN}_1") (pintype "passive"))
    )
    (net (code "99") (name "/USB_VID_N") (class "Default")
      (node (ref "JP10L") (pin "47") (pintype "passive"))
    )
    (net (code "100") (name "/USB_VID_P") (class "Default")
      (node (ref "JP10L") (pin "48") (pintype "passive"))
    )
    (net (code "101") (name "/USB_VID_P5V") (class "Default")
      (node (ref "C16L") (pin "1") (pinfunction "1_1") (pintype "passive"))
      (node (ref "JP10L") (pin "46") (pintype "passive"))
      (node (ref "U10L") (pin "5") (pinfunction "VOUT_5") (pintype "passive"))
    )
    (net (code "102") (name "GND") (class "Default")
      (node (ref "C10L") (pin "2") (pinfunction "2_2") (pintype "passive"))
      (node (ref "C11L") (pin "2") (pinfunction "2_2") (pintype "passive"))
      (node (ref "C12L") (pin "2") (pinfunction "2_2") (pintype "passive"))
      (node (ref "C13L") (pin "2") (pinfunction "2_2") (pintype "passive"))
      (node (ref "C15L") (pin "2") (pinfunction "2_2") (pintype "passive"))
      (node (ref "C16L") (pin "2") (pinfunction "2_2") (pintype "passive"))
      (node (ref "C17L") (pin "2") (pinfunction "2_2") (pintype "passive"))
      (node (ref "C18L") (pin "2") (pinfunction "2_2") (pintype "passive"))
      (node (ref "C20L") (pin "2") (pinfunction "2_2") (pintype "passive"))
      (node (ref "C21L") (pin "2") (pinfunction "2_2") (pintype "passive"))
      (node (ref "C22L") (pin "2") (pinfunction "2_2") (pintype "passive"))
      (node (ref "C23L") (pin "2") (pinfunction "2_2") (pintype "passive"))
      (node (ref "D10L") (pin "3") (pinfunction "GND1_3") (pintype "input"))
      (node (ref "D11L") (pin "3") (pinfunction "GND1_3") (pintype "input"))
      (node (ref "D12L") (pin "3") (pinfunction "GND1_3") (pintype "input"))
      (node (ref "D13L") (pin "2") (pinfunction "A_2") (pintype "passive"))
      (node (ref "J10L") (pin "0") (pinfunction "GND_0") (pintype "passive"))
      (node (ref "J10L") (pin "11") (pinfunction "11_11") (pintype "passive"))
      (node (ref "J10L") (pin "17") (pinfunction "17_17") (pintype "passive"))
      (node (ref "J10L") (pin "2") (pinfunction "2_2") (pintype "passive"))
      (node (ref "J10L") (pin "5") (pinfunction "5_5") (pintype "passive"))
      (node (ref "J10L") (pin "8") (pinfunction "8_8") (pintype "passive"))
      (node (ref "JP10L") (pin "12") (pintype "passive"))
      (node (ref "JP10L") (pin "15") (pintype "passive"))
      (node (ref "JP10L") (pin "18") (pintype "passive"))
      (node (ref "JP10L") (pin "21") (pintype "passive"))
      (node (ref "JP10L") (pin "24") (pintype "passive"))
      (node (ref "JP10L") (pin "27") (pintype "passive"))
      (node (ref "JP10L") (pin "30") (pintype "passive"))
      (node (ref "JP10L") (pin "33") (pintype "passive"))
      (node (ref "JP10L") (pin "36") (pintype "passive"))
      (node (ref "JP10L") (pin "39") (pintype "passive"))
      (node (ref "JP10L") (pin "44") (pintype "passive"))
      (node (ref "JP10L") (pin "45") (pintype "passive"))
      (node (ref "JP10L") (pin "49") (pintype "passive"))
      (node (ref "JP10L") (pin "9") (pintype "passive"))
      (node (ref "Q12L") (pin "2") (pinfunction "S_2") (pintype "passive"))
      (node (ref "Q13L") (pin "2") (pinfunction "S_2") (pintype "passive"))
      (node (ref "Q14L") (pin "2") (pinfunction "S_2") (pintype "passive"))
      (node (ref "Q15L") (pin "2") (pinfunction "S_2") (pintype "passive"))
      (node (ref "Q17L") (pin "2") (pinfunction "S_2") (pintype "passive"))
      (node (ref "Q18L") (pin "2") (pinfunction "S_2") (pintype "passive"))
      (node (ref "Q19L") (pin "2") (pinfunction "S_2") (pintype "passive"))
      (node (ref "R13L") (pin "2") (pinfunction "2_2") (pintype "passive"))
      (node (ref "R14L") (pin "2") (pinfunction "2_2") (pintype "passive"))
      (node (ref "R18L") (pin "1") (pinfunction "1_1") (pintype "passive"))
      (node (ref "R24L") (pin "1") (pinfunction "1_1") (pintype "passive"))
      (node (ref "R25L") (pin "2") (pinfunction "B_2") (pintype "bidirectional"))
      (node (ref "U10L") (pin "2") (pinfunction "GND_2") (pintype "power_in"))
    )
    (net (code "103") (name "Net-(J10L-Pad13)") (class "Default")
      (node (ref "J10L") (pin "13") (pinfunction "13_13") (pintype "passive"))
      (node (ref "R31L") (pin "1") (pinfunction "1_1") (pintype "passive"))
    )
    (net (code "104") (name "Net-(J10L-Pad19)") (class "Default")
      (node (ref "J10L") (pin "19") (pinfunction "19_19") (pintype "passive"))
      (node (ref "R32L") (pin "1") (pinfunction "1_1") (pintype "passive"))
    )
    (net (code "105") (name "Net-(Q10L-G)") (class "Default")
      (node (ref "C14L") (pin "2") (pinfunction "2_2") (pintype "passive"))
      (node (ref "Q10L") (pin "4") (pinfunction "G_4") (pintype "passive"))
      (node (ref "R11L") (pin "1") (pinfunction "1_1") (pintype "passive"))
      (node (ref "R15L") (pin "1") (pinfunction "1_1") (pintype "passive"))
    )
    (net (code "106") (name "Net-(Q11L-G)") (class "Default")
      (node (ref "C19L") (pin "2") (pinfunction "2_2") (pintype "passive"))
      (node (ref "Q11L") (pin "4") (pinfunction "G_4") (pintype "passive"))
      (node (ref "R16L") (pin "1") (pinfunction "1_1") (pintype "passive"))
      (node (ref "R19L") (pin "1") (pinfunction "1_1") (pintype "passive"))
    )
    (net (code "107") (name "Net-(Q12L-D)") (class "Default")
      (node (ref "Q12L") (pin "3") (pinfunction "D_3") (pintype "passive"))
      (node (ref "Q13L") (pin "1") (pinfunction "G_1") (pintype "passive"))
      (node (ref "R15L") (pin "2") (pinfunction "2_2") (pintype "passive"))
    )
    (net (code "108") (name "Net-(Q13L-D)") (class "Default")
      (node (ref "Q13L") (pin "3") (pinfunction "D_3") (pintype "passive"))
      (node (ref "Q14L") (pin "1") (pinfunction "G_1") (pintype "passive"))
      (node (ref "R17L") (pin "1") (pinfunction "1_1") (pintype "passive"))
    )
    (net (code "109") (name "Net-(Q14L-D)") (class "Default")
      (node (ref "Q14L") (pin "3") (pinfunction "D_3") (pintype "passive"))
      (node (ref "R19L") (pin "2") (pinfunction "2_2") (pintype "passive"))
    )
    (net (code "110") (name "Net-(Q15L-D)") (class "Default")
      (node (ref "Q15L") (pin "3") (pinfunction "D_3") (pintype "passive"))
      (node (ref "Q19L") (pin "1") (pinfunction "G_1") (pintype "passive"))
      (node (ref "R33L") (pin "2") (pinfunction "2_2") (pintype "passive"))
    )
    (net (code "111") (name "P3.3V") (class "Default")
      (node (ref "C10L") (pin "1") (pinfunction "1_1") (pintype "passive"))
      (node (ref "Q16L") (pin "1") (pinfunction "G_1") (pintype "passive"))
      (node (ref "R20L") (pin "1") (pinfunction "1_1") (pintype "passive"))
      (node (ref "R23L") (pin "1") (pinfunction "1_1") (pintype "passive"))
      (node (ref "R33L") (pin "1") (pinfunction "1_1") (pintype "passive"))
    )
    (net (code "112") (name "P3.3V_DELAYED") (class "Default")
      (node (ref "C14L") (pin "1") (pinfunction "1_1") (pintype "passive"))
      (node (ref "Q10L") (pin "1") (pinfunction "S_1") (pintype "passive"))
      (node (ref "Q10L") (pin "2") (pinfunction "S_2") (pintype "passive"))
      (node (ref "Q10L") (pin "3") (pinfunction "S_3") (pintype "passive"))
      (node (ref "R11L") (pin "2") (pinfunction "2_2") (pintype "passive"))
      (node (ref "R12L") (pin "2") (pinfunction "2_2") (pintype "passive"))
      (node (ref "R29L") (pin "1") (pinfunction "1_1") (pintype "passive"))
      (node (ref "R30L") (pin "1") (pinfunction "1_1") (pintype "passive"))
    )
    (net (code "113") (name "P5.0V_DELAYED") (class "Default")
      (node (ref "C15L") (pin "1") (pinfunction "1_1") (pintype "passive"))
      (node (ref "F10L") (pin "1") (pinfunction "1_1") (pintype "bidirectional"))
      (node (ref "R21L") (pin "1") (pinfunction "1_1") (pintype "passive"))
      (node (ref "R22L") (pin "1") (pinfunction "1_1") (pintype "passive"))
      (node (ref "U10L") (pin "4") (pinfunction "VIN_4") (pintype "passive"))
    )
    (net (code "114") (name "VDDSOC_CAP") (class "Default")
      (node (ref "C20L") (pin "1") (pinfunction "1_1") (pintype "passive"))
      (node (ref "C21L") (pin "1") (pinfunction "1_1") (pintype "passive"))
      (node (ref "U100") (pin "L7") (pinfunction "HDMI_VP_L7") (pintype "power_in"))
    )
    (net (code "115") (name "VDD_HIGH_CAP") (class "Default")
      (node (ref "C11L") (pin "1") (pinfunction "1_1") (pintype "passive"))
      (node (ref "C22L") (pin "1") (pinfunction "1_1") (pintype "passive"))
      (node (ref "C23L") (pin "1") (pinfunction "1_1") (pintype "passive"))
      (node (ref "U100") (pin "M7") (pinfunction "HDMI_VPH_M7") (pintype "power_in"))
      (node (ref "U100") (pin "V7") (pinfunction "NVCC_LVDS2P5_V7") (pintype "power_in"))
    )
    (net (code "116") (name "unconnected-(J10L-Pad14)") (class "Default")
      (node (ref "J10L") (pin "14") (pinfunction "14_14") (pintype "passive"))
    )
    (net (code "117") (name "unconnected-(U100D-CSI0_DAT14-PadM4)") (class "Default")
      (node (ref "U100") (pin "M4") (pinfunction "CSI0_DAT14_M4") (pintype "bidirectional"))
    )
    (net (code "118") (name "unconnected-(U100D-CSI0_DAT15-PadM5)") (class "Default")
      (node (ref "U100") (pin "M5") (pinfunction "CSI0_DAT15_M5") (pintype "bidirectional"))
    )
    (net (code "119") (name "unconnected-(U100D-CSI0_DAT18-PadM6)") (class "Default")
      (node (ref "U100") (pin "M6") (pinfunction "CSI0_DAT18_M6") (pintype "bidirectional"))
    )
    (net (code "120") (name "unconnected-(U100D-CSI0_DAT19-PadL6)") (class "Default")
      (node (ref "U100") (pin "L6") (pinfunction "CSI0_DAT19_L6") (pintype "bidirectional"))
    )
    (net (code "121") (name "unconnected-(U100D-CSI0_PIXCLK-PadP1)") (class "Default")
      (node (ref "U100") (pin "P1") (pinfunction "CSI0_PIXCLK_P1") (pintype "bidirectional"))
    )
    (net (code "122") (name "unconnected-(U100D-CSI_CLK0M-PadF4)") (class "Default")
      (node (ref "U100") (pin "F4") (pinfunction "CSI_CLK0M_F4") (pintype "input+no_connect"))
    )
    (net (code "123") (name "unconnected-(U100D-CSI_CLK0P-PadF3)") (class "Default")
      (node (ref "U100") (pin "F3") (pinfunction "CSI_CLK0P_F3") (pintype "input+no_connect"))
    )
    (net (code "124") (name "unconnected-(U100D-CSI_D0M-PadE4)") (class "Default")
      (node (ref "U100") (pin "E4") (pinfunction "CSI_D0M_E4") (pintype "input+no_connect"))
    )
    (net (code "125") (name "unconnected-(U100D-CSI_D0P-PadE3)") (class "Default")
      (node (ref "U100") (pin "E3") (pinfunction "CSI_D0P_E3") (pintype "input+no_connect"))
    )
    (net (code "126") (name "unconnected-(U100D-CSI_D1M-PadD1)") (class "Default")
      (node (ref "U100") (pin "D1") (pinfunction "CSI_D1M_D1") (pintype "input+no_connect"))
    )
    (net (code "127") (name "unconnected-(U100D-CSI_D1P-PadD2)") (class "Default")
      (node (ref "U100") (pin "D2") (pinfunction "CSI_D1P_D2") (pintype "input+no_connect"))
    )
    (net (code "128") (name "unconnected-(U100D-CSI_D2M-PadE1)") (class "Default")
      (node (ref "U100") (pin "E1") (pinfunction "CSI_D2M_E1") (pintype "input+no_connect"))
    )
    (net (code "129") (name "unconnected-(U100D-CSI_D2P-PadE2)") (class "Default")
      (node (ref "U100") (pin "E2") (pinfunction "CSI_D2P_E2") (pintype "input+no_connect"))
    )
    (net (code "130") (name "unconnected-(U100D-CSI_D3M-PadF2)") (class "Default")
      (node (ref "U100") (pin "F2") (pinfunction "CSI_D3M_F2") (pintype "input+no_connect"))
    )
    (net (code "131") (name "unconnected-(U100D-CSI_D3P-PadF1)") (class "Default")
      (node (ref "U100") (pin "F1") (pinfunction "CSI_D3P_F1") (pintype "input+no_connect"))
    )
    (net (code "132") (name "unconnected-(U100D-DI0_DISP_CLK-PadN19)") (class "Default")
      (node (ref "U100") (pin "N19") (pinfunction "DI0_DISP_CLK_N19") (pintype "bidirectional"))
    )
    (net (code "133") (name "unconnected-(U100D-DSI_CLK0M-PadH3)") (class "Default")
      (node (ref "U100") (pin "H3") (pinfunction "DSI_CLK0M_H3") (pintype "output"))
    )
    (net (code "134") (name "unconnected-(U100D-DSI_CLK0P-PadH4)") (class "Default")
      (node (ref "U100") (pin "H4") (pinfunction "DSI_CLK0P_H4") (pintype "output"))
    )
    (net (code "135") (name "unconnected-(U100D-DSI_D0M-PadG2)") (class "Default")
      (node (ref "U100") (pin "G2") (pinfunction "DSI_D0M_G2") (pintype "output"))
    )
    (net (code "136") (name "unconnected-(U100D-DSI_D0P-PadG1)") (class "Default")
      (node (ref "U100") (pin "G1") (pinfunction "DSI_D0P_G1") (pintype "output"))
    )
    (net (code "137") (name "unconnected-(U100D-DSI_D1M-PadH2)") (class "Default")
      (node (ref "U100") (pin "H2") (pinfunction "DSI_D1M_H2") (pintype "output"))
    )
    (net (code "138") (name "unconnected-(U100D-DSI_D1P-PadH1)") (class "Default")
      (node (ref "U100") (pin "H1") (pinfunction "DSI_D1P_H1") (pintype "output"))
    )
  )
)
